# FEU31_Part3.net
KiCad netlist of a schematic drawn in Altium Designer
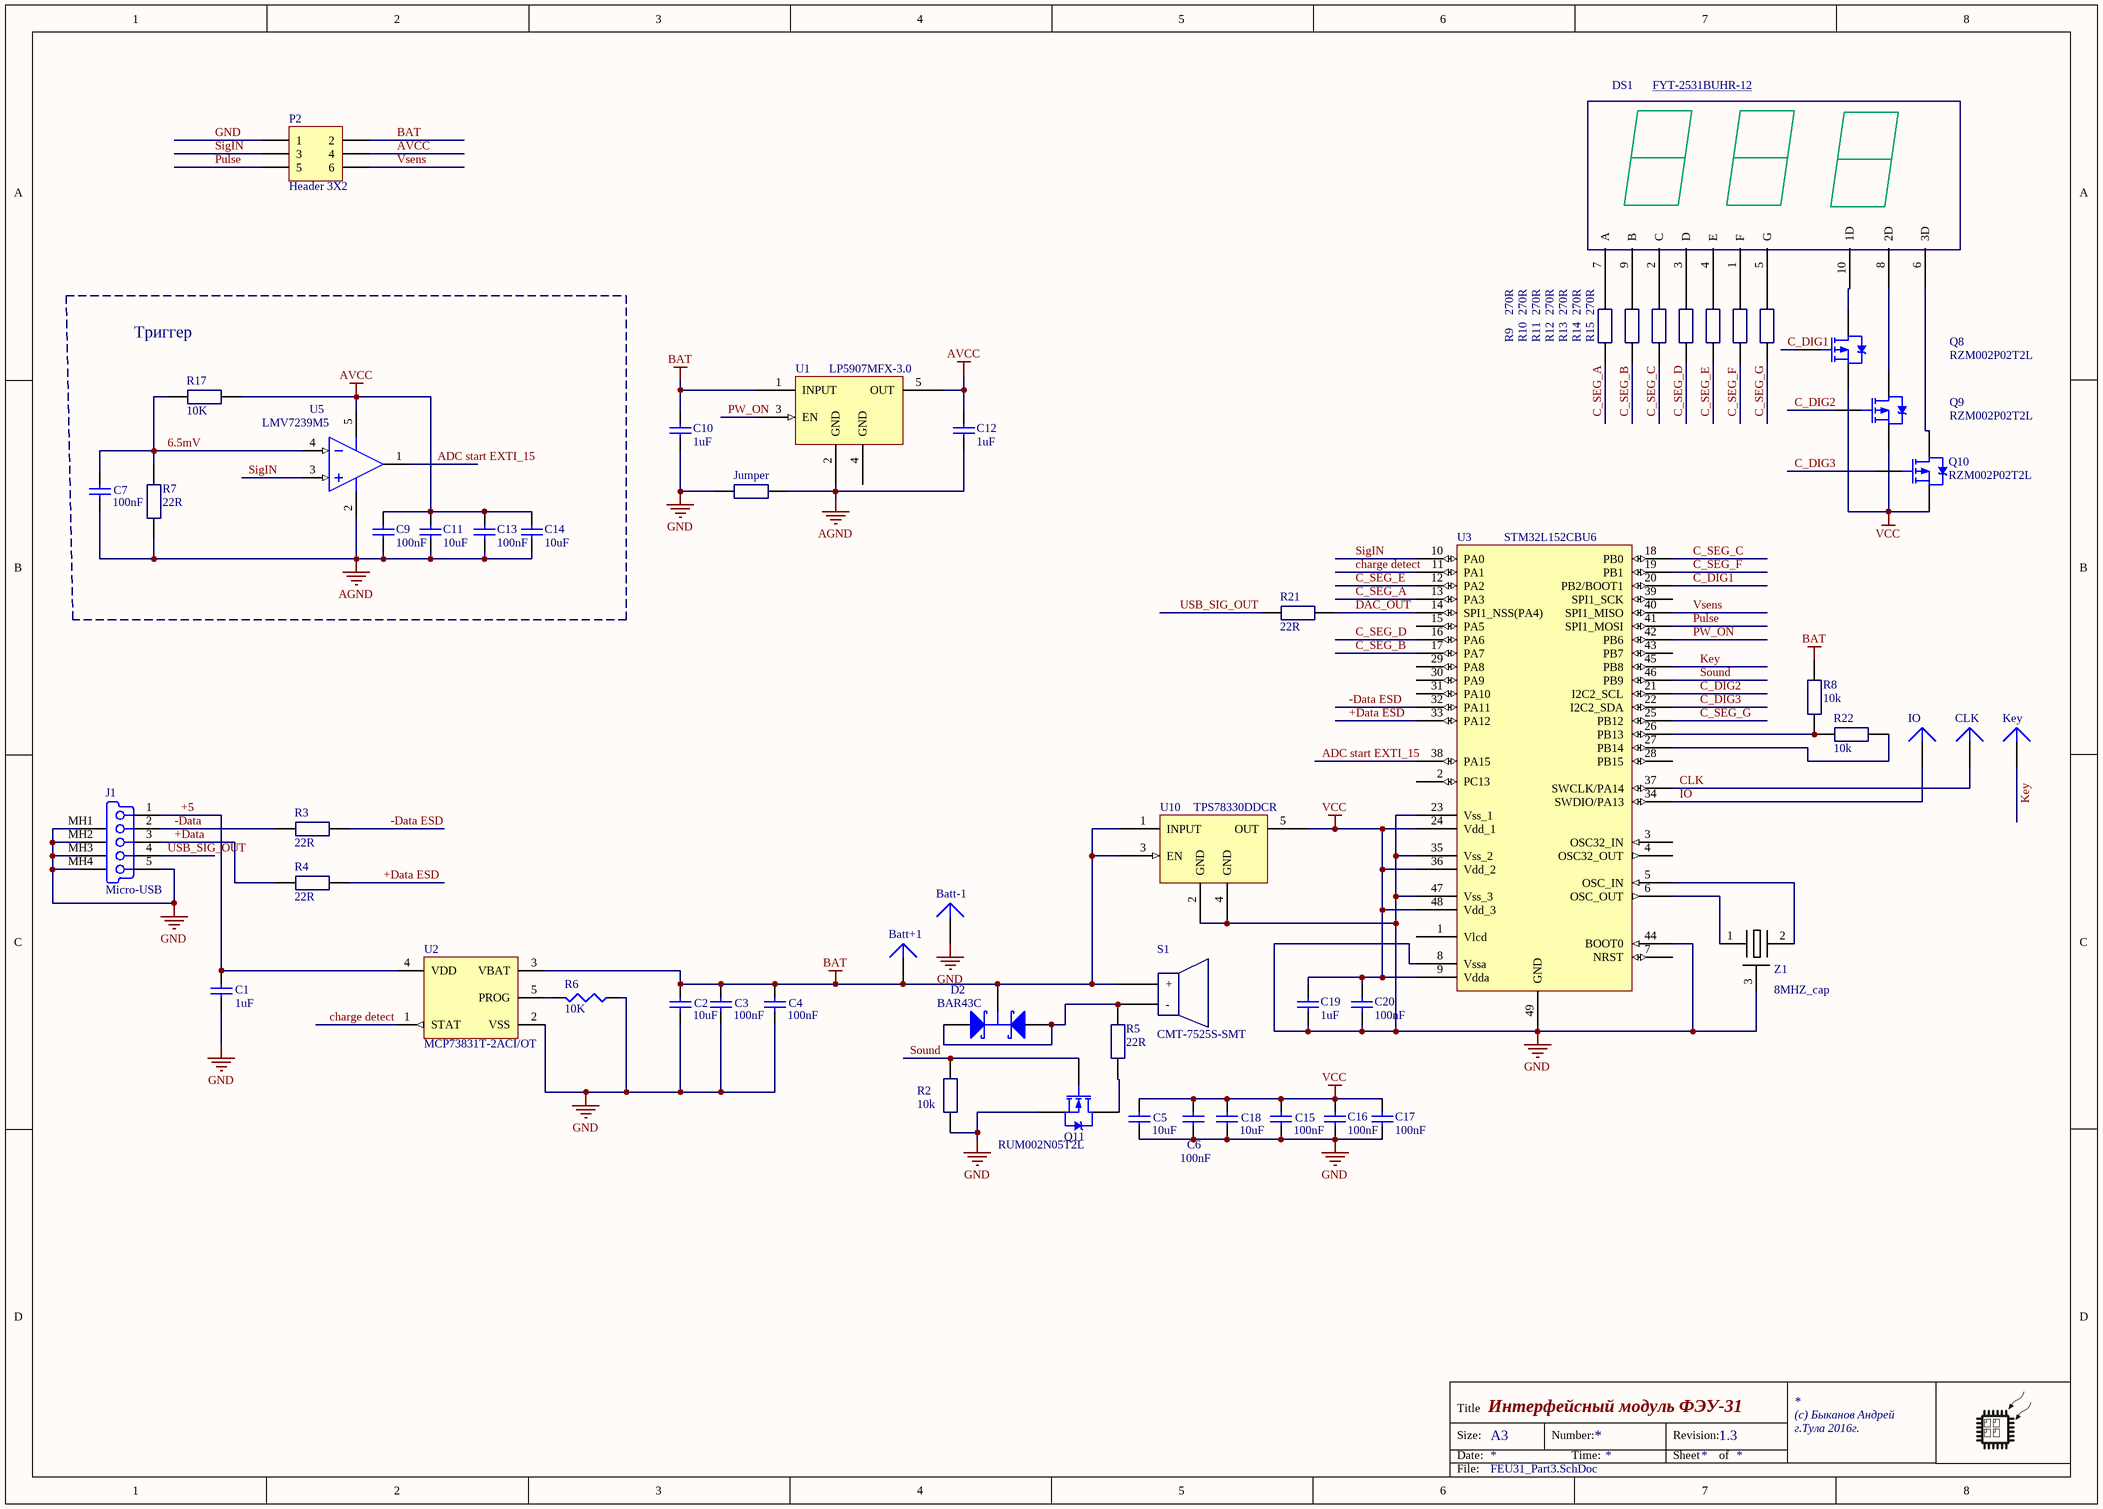
[diagram p0: FEU31_Part3.SchDoc]

(export (version "E")
  (design (tool "Eeschema 10.0.6"))
  (components
    (comp (ref "Batt+1")
      (value "~")
      (footprint "Sensor contact")
      (description "Plug")
      (fields (field (name "PUBLISHER") "Altium Limited"))
      (libsource (lib "Miscellaneous Connectors") (part "Plug"))
    )
    (comp (ref "Batt-1")
      (value "~")
      (footprint "Sensor contact")
      (description "Plug")
      (fields (field (name "PUBLISHER") "Altium Limited"))
      (libsource (lib "Miscellaneous Connectors") (part "Plug"))
    )
    (comp (ref "C1")
      (value "1uF")
      (footprint "0402 AVX")
      (description "Capacitor (Semiconductor SIM Model)")
      (fields (field (name "PUBLISHER") "Altium Limited"))
      (libsource (lib "Miscellaneous Devices") (part "Cap Semi"))
    )
    (comp (ref "C2")
      (value "10uF")
      (footprint "1608[0603]")
      (description "Capacitor (Semiconductor SIM Model)")
      (fields (field (name "PUBLISHER") "Altium Limited"))
      (libsource (lib "Miscellaneous Devices") (part "Cap Semi"))
    )
    (comp (ref "C3")
      (value "100nF")
      (footprint "0402 AVX")
      (description "Capacitor (Semiconductor SIM Model)")
      (fields (field (name "PUBLISHER") "Altium Limited"))
      (libsource (lib "Miscellaneous Devices") (part "Cap Semi"))
    )
    (comp (ref "C4")
      (value "100nF")
      (footprint "0402 AVX")
      (description "Capacitor (Semiconductor SIM Model)")
      (fields (field (name "PUBLISHER") "Altium Limited"))
      (libsource (lib "Miscellaneous Devices") (part "Cap Semi"))
    )
    (comp (ref "C5")
      (value "10uF")
      (footprint "1608[0603]")
      (description "Capacitor (Semiconductor SIM Model)")
      (fields (field (name "PUBLISHER") "Altium Limited"))
      (libsource (lib "Miscellaneous Devices") (part "Cap Semi"))
    )
    (comp (ref "C6")
      (value "100nF")
      (footprint "0402 AVX")
      (description "Capacitor (Semiconductor SIM Model)")
      (fields (field (name "PUBLISHER") "Altium Limited"))
      (libsource (lib "Miscellaneous Devices") (part "Cap Semi"))
    )
    (comp (ref "C7")
      (value "100nF")
      (footprint "0402 AVX")
      (description "Capacitor (Semiconductor SIM Model)")
      (fields (field (name "PUBLISHER") "Altium Limited"))
      (libsource (lib "Miscellaneous Devices") (part "Cap Semi"))
    )
    (comp (ref "C9")
      (value "100nF")
      (footprint "0402 AVX")
      (description "Capacitor (Semiconductor SIM Model)")
      (fields (field (name "PUBLISHER") "Altium Limited"))
      (libsource (lib "Miscellaneous Devices") (part "Cap Semi"))
    )
    (comp (ref "C10")
      (value "1uF")
      (footprint "0402 AVX")
      (description "Capacitor (Semiconductor SIM Model)")
      (fields (field (name "PUBLISHER") "Altium Limited"))
      (libsource (lib "Miscellaneous Devices") (part "Cap Semi"))
    )
    (comp (ref "C11")
      (value "10uF")
      (footprint "1608[0603]")
      (description "Capacitor (Semiconductor SIM Model)")
      (fields (field (name "PUBLISHER") "Altium Limited"))
      (libsource (lib "Miscellaneous Devices") (part "Cap Semi"))
    )
    (comp (ref "C12")
      (value "1uF")
      (footprint "0402 AVX")
      (description "Capacitor (Semiconductor SIM Model)")
      (fields (field (name "PUBLISHER") "Altium Limited"))
      (libsource (lib "Miscellaneous Devices") (part "Cap Semi"))
    )
    (comp (ref "C13")
      (value "100nF")
      (footprint "0402 AVX")
      (description "Capacitor (Semiconductor SIM Model)")
      (fields (field (name "PUBLISHER") "Altium Limited"))
      (libsource (lib "Miscellaneous Devices") (part "Cap Semi"))
    )
    (comp (ref "C14")
      (value "10uF")
      (footprint "1608[0603]")
      (description "Capacitor (Semiconductor SIM Model)")
      (fields (field (name "PUBLISHER") "Altium Limited"))
      (libsource (lib "Miscellaneous Devices") (part "Cap Semi"))
    )
    (comp (ref "C15")
      (value "100nF")
      (footprint "0402 AVX")
      (description "Capacitor (Semiconductor SIM Model)")
      (fields (field (name "PUBLISHER") "Altium Limited"))
      (libsource (lib "Miscellaneous Devices") (part "Cap Semi"))
    )
    (comp (ref "C16")
      (value "100nF")
      (footprint "0402 AVX")
      (description "Capacitor (Semiconductor SIM Model)")
      (fields (field (name "PUBLISHER") "Altium Limited"))
      (libsource (lib "Miscellaneous Devices") (part "Cap Semi"))
    )
    (comp (ref "C17")
      (value "100nF")
      (footprint "0402 AVX")
      (description "Capacitor (Semiconductor SIM Model)")
      (fields (field (name "PUBLISHER") "Altium Limited"))
      (libsource (lib "Miscellaneous Devices") (part "Cap Semi"))
    )
    (comp (ref "C18")
      (value "10uF")
      (footprint "1608[0603]")
      (description "Capacitor (Semiconductor SIM Model)")
      (fields (field (name "PUBLISHER") "Altium Limited"))
      (libsource (lib "Miscellaneous Devices") (part "Cap Semi"))
    )
    (comp (ref "C19")
      (value "1uF")
      (footprint "0402 AVX")
      (description "Capacitor (Semiconductor SIM Model)")
      (fields (field (name "PUBLISHER") "Altium Limited"))
      (libsource (lib "Miscellaneous Devices") (part "Cap Semi"))
    )
    (comp (ref "C20")
      (value "100nF")
      (footprint "0402 AVX")
      (description "Capacitor (Semiconductor SIM Model)")
      (fields (field (name "PUBLISHER") "Altium Limited"))
      (libsource (lib "Miscellaneous Devices") (part "Cap Semi"))
    )
    (comp (ref "CLK")
      (value "~")
      (footprint "Sensor contact")
      (description "Plug")
      (fields (field (name "PUBLISHER") "Altium Limited"))
      (libsource (lib "Miscellaneous Connectors") (part "Plug"))
    )
    (comp (ref "D2")
      (value "BAR43C")
      (footprint "SOT23-3")
      (description "Schottky Barrier Double Diode")
      (fields (field (name "PUBLISHER") "Altium Limited"))
      (libsource (lib "Philips Discrete Diode - Schottky") (part "BAT54C"))
    )
    (comp (ref "DS1")
      (value "FYT-2531BUHR-12")
      (footprint "FYT-2531BUHR-12")
      (description "7-segment 3x indicator")
      (libsource (lib "My SCH library") (part "FYT-2531BUHR-12_1"))
    )
    (comp (ref "IO")
      (value "~")
      (footprint "Sensor contact")
      (description "Plug")
      (fields (field (name "PUBLISHER") "Altium Limited"))
      (libsource (lib "Miscellaneous Connectors") (part "Plug"))
    )
    (comp (ref "J1")
      (value "Micro-USB")
      (footprint "47346-0001")
      (libsource (lib "Molex Serial Bus Mini USB") (part "0481900001"))
    )
    (comp (ref "Jumper")
      (value "~")
      (footprint "0402 jumper")
      (libsource (lib "Микрон-3") (part "Resistor 0805"))
    )
    (comp (ref "Key")
      (value "~")
      (footprint "Sensor contact")
      (description "Plug")
      (fields (field (name "PUBLISHER") "Altium Limited"))
      (libsource (lib "Miscellaneous Connectors") (part "Plug"))
    )
    (comp (ref "P2")
      (value "Header 3X2")
      (footprint "PLS_FLAT_CONN_6")
      (description "Header, 3-Pin, Dual row")
      (fields (field (name "PUBLISHER") "Altium Limited"))
      (libsource (lib "Miscellaneous Connectors") (part "Header 3X2"))
    )
    (comp (ref "Q8")
      (value "RZM002P02T2L")
      (footprint "RUM002N05")
      (description "HEXFET Power MOSFET")
      (fields (field (name "PUBLISHER") "Altium Limited"))
      (libsource (lib "IR Discrete MOSFET - Power") (part "IRLML6401"))
    )
    (comp (ref "Q9")
      (value "RZM002P02T2L")
      (footprint "RUM002N05")
      (description "HEXFET Power MOSFET")
      (fields (field (name "PUBLISHER") "Altium Limited"))
      (libsource (lib "IR Discrete MOSFET - Power") (part "IRLML6401"))
    )
    (comp (ref "Q10")
      (value "RZM002P02T2L")
      (footprint "RUM002N05")
      (description "HEXFET Power MOSFET")
      (fields (field (name "PUBLISHER") "Altium Limited"))
      (libsource (lib "IR Discrete MOSFET - Power") (part "IRLML6401"))
    )
    (comp (ref "Q11")
      (value "RUM002N05T2L")
      (footprint "RUM002N05")
      (description "HEXFET Power MOSFET")
      (fields (field (name "PUBLISHER") "Altium Limited"))
      (libsource (lib "IR Discrete MOSFET - Power") (part "IRLML2402"))
    )
    (comp (ref "R2")
      (value "10k")
      (footprint "1608[0603]")
      (libsource (lib "Микрон-3") (part "Resistor 0805"))
    )
    (comp (ref "R3")
      (value "22R")
      (footprint "1608[0603]")
      (libsource (lib "Микрон-3") (part "Resistor 0805"))
    )
    (comp (ref "R4")
      (value "22R")
      (footprint "1608[0603]")
      (libsource (lib "Микрон-3") (part "Resistor 0805"))
    )
    (comp (ref "R5")
      (value "22R")
      (footprint "1608[0603]")
      (libsource (lib "Микрон-3") (part "Resistor 0805"))
    )
    (comp (ref "R6")
      (value "10K")
      (footprint "J1-0603")
      (description "Resistor")
      (fields (field (name "PUBLISHER") "Altium Limited"))
      (libsource (lib "Miscellaneous Devices") (part "Res3"))
    )
    (comp (ref "R7")
      (value "22R")
      (footprint "1608[0603]")
      (libsource (lib "Микрон-3") (part "Resistor 0805"))
    )
    (comp (ref "R8")
      (value "10k")
      (footprint "1608[0603]")
      (libsource (lib "Микрон-3") (part "Resistor 0805"))
    )
    (comp (ref "R9")
      (value "270R")
      (footprint "1608[0603]")
      (libsource (lib "Микрон-3") (part "Resistor 0805"))
    )
    (comp (ref "R10")
      (value "270R")
      (footprint "1608[0603]")
      (libsource (lib "Микрон-3") (part "Resistor 0805"))
    )
    (comp (ref "R11")
      (value "270R")
      (footprint "1608[0603]")
      (libsource (lib "Микрон-3") (part "Resistor 0805"))
    )
    (comp (ref "R12")
      (value "270R")
      (footprint "1608[0603]")
      (libsource (lib "Микрон-3") (part "Resistor 0805"))
    )
    (comp (ref "R13")
      (value "270R")
      (footprint "1608[0603]")
      (libsource (lib "Микрон-3") (part "Resistor 0805"))
    )
    (comp (ref "R14")
      (value "270R")
      (footprint "1608[0603]")
      (libsource (lib "Микрон-3") (part "Resistor 0805"))
    )
    (comp (ref "R15")
      (value "270R")
      (footprint "1608[0603]")
      (libsource (lib "Микрон-3") (part "Resistor 0805"))
    )
    (comp (ref "R17")
      (value "10K")
      (footprint "1608[0603]")
      (libsource (lib "Микрон-3") (part "Resistor 0805"))
    )
    (comp (ref "R21")
      (value "22R")
      (footprint "1608[0603]_RES")
      (libsource (lib "Микрон-3") (part "Resistor 0805"))
    )
    (comp (ref "R22")
      (value "10k")
      (footprint "1608[0603]")
      (libsource (lib "Микрон-3") (part "Resistor 0805"))
    )
    (comp (ref "S1")
      (value "CMT-7525S-SMT")
      (footprint "CMT-7525S-SMT")
      (libsource (lib "My SCH library") (part "CMT-7525S-SMT"))
    )
    (comp (ref "U1")
      (value "LP5907MFX-3.0")
      (footprint "TPS78330DDCR")
      (libsource (lib "My SCH library") (part "TPS78330DDCR"))
    )
    (comp (ref "U2")
      (value "MCP73831T-2ACI/OT")
      (footprint "SOT-23-OT5_N")
      (fields (field (name "PUBLISHER") "Altium Limited"))
      (libsource (lib "Microchip Power Mgt Battery Management") (part "MCP73831T-2ACI/OT"))
    )
    (comp (ref "U3")
      (value "STM32L152CBU6")
      (footprint "UFQFPN48")
      (libsource (lib "Micron-3.2") (part "STM32L152CBU6"))
    )
    (comp (ref "U5")
      (value "LMV7239M5")
      (footprint "MF05A_N")
      (fields
        (field (name "MANUFACTURER") "National Semiconductor")
        (field (name "PUBLISHER") "Altium Limited")
      )
      (libsource (lib "NSC Amplifier") (part "LMV7239M5"))
    )
    (comp (ref "U10")
      (value "TPS78330DDCR")
      (footprint "TPS78330DDCR")
      (libsource (lib "My SCH library") (part "TPS78330DDCR"))
    )
    (comp (ref "Z1")
      (value "8MHZ_cap")
      (footprint "PRQV8.00CR5010Y000")
      (libsource (lib "My SCH library") (part "8MHZ_cap"))
    )
  )
  (nets
    (net (code "1") (name "/+5") (class "Default")
      (node (ref "C1") (pin "2") (pinfunction "2_2") (pintype "passive"))
      (node (ref "J1") (pin "1") (pinfunction "V_BUS_(5V)_1") (pintype "passive"))
      (node (ref "U2") (pin "4") (pinfunction "VDD_4") (pintype "power_in"))
    )
    (net (code "2") (name "/+Data") (class "Default")
      (node (ref "J1") (pin "3") (pinfunction "D+_3") (pintype "passive"))
      (node (ref "R4") (pin "2") (pinfunction "2_2") (pintype "passive"))
    )
    (net (code "3") (name "/+Data ESD") (class "Default")
      (node (ref "R4") (pin "1") (pinfunction "A_1") (pintype "passive"))
      (node (ref "U3") (pin "33") (pinfunction "PA12_33") (pintype "bidirectional"))
    )
    (net (code "4") (name "/-Data") (class "Default")
      (node (ref "J1") (pin "2") (pinfunction "D-_2") (pintype "passive"))
      (node (ref "R3") (pin "2") (pinfunction "2_2") (pintype "passive"))
    )
    (net (code "5") (name "/-Data ESD") (class "Default")
      (node (ref "R3") (pin "1") (pinfunction "A_1") (pintype "passive"))
      (node (ref "U3") (pin "32") (pinfunction "PA11_32") (pintype "bidirectional"))
    )
    (net (code "6") (name "/6.5mV") (class "Default")
      (node (ref "C7") (pin "1") (pinfunction "1_1") (pintype "passive"))
      (node (ref "R17") (pin "1") (pinfunction "A_1") (pintype "passive"))
      (node (ref "R7") (pin "2") (pinfunction "2_2") (pintype "passive"))
      (node (ref "U5") (pin "4") (pinfunction "IN-_4") (pintype "input"))
    )
    (net (code "7") (name "/ADC start EXTI_15") (class "Default")
      (node (ref "U3") (pin "38") (pinfunction "PA15_38") (pintype "bidirectional"))
      (node (ref "U5") (pin "1") (pinfunction "VOUT_1") (pintype "open_collector"))
    )
    (net (code "8") (name "/CLK") (class "Default")
      (node (ref "CLK") (pin "1") (pinfunction "1_1") (pintype "passive"))
      (node (ref "U3") (pin "37") (pinfunction "SWCLK/PA14_37") (pintype "bidirectional"))
    )
    (net (code "9") (name "/C_DIG1") (class "Default")
      (node (ref "Q8") (pin "1") (pinfunction "G_1") (pintype "passive"))
      (node (ref "U3") (pin "20") (pinfunction "PB2/BOOT1_20") (pintype "bidirectional"))
    )
    (net (code "10") (name "/C_DIG2") (class "Default")
      (node (ref "Q9") (pin "1") (pinfunction "G_1") (pintype "passive"))
      (node (ref "U3") (pin "21") (pinfunction "I2C2_SCL_21") (pintype "bidirectional"))
    )
    (net (code "11") (name "/C_DIG3") (class "Default")
      (node (ref "Q10") (pin "1") (pinfunction "G_1") (pintype "passive"))
      (node (ref "U3") (pin "22") (pinfunction "I2C2_SDA_22") (pintype "bidirectional"))
    )
    (net (code "12") (name "/C_SEG_A") (class "Default")
      (node (ref "R12") (pin "2") (pinfunction "2_2") (pintype "passive"))
      (node (ref "U3") (pin "13") (pinfunction "PA3_13") (pintype "bidirectional"))
    )
    (net (code "13") (name "/C_SEG_B") (class "Default")
      (node (ref "R13") (pin "2") (pinfunction "2_2") (pintype "passive"))
      (node (ref "U3") (pin "17") (pinfunction "PA7_17") (pintype "bidirectional"))
    )
    (net (code "14") (name "/C_SEG_C") (class "Default")
      (node (ref "R11") (pin "2") (pinfunction "2_2") (pintype "passive"))
      (node (ref "U3") (pin "18") (pinfunction "PB0_18") (pintype "bidirectional"))
    )
    (net (code "15") (name "/C_SEG_D") (class "Default")
      (node (ref "R14") (pin "2") (pinfunction "2_2") (pintype "passive"))
      (node (ref "U3") (pin "16") (pinfunction "PA6_16") (pintype "bidirectional"))
    )
    (net (code "16") (name "/C_SEG_E") (class "Default")
      (node (ref "R10") (pin "2") (pinfunction "2_2") (pintype "passive"))
      (node (ref "U3") (pin "12") (pinfunction "PA2_12") (pintype "bidirectional"))
    )
    (net (code "17") (name "/C_SEG_F") (class "Default")
      (node (ref "R15") (pin "2") (pinfunction "2_2") (pintype "passive"))
      (node (ref "U3") (pin "19") (pinfunction "PB1_19") (pintype "bidirectional"))
    )
    (net (code "18") (name "/C_SEG_G") (class "Default")
      (node (ref "R9") (pin "2") (pinfunction "2_2") (pintype "passive"))
      (node (ref "U3") (pin "25") (pinfunction "PB12_25") (pintype "bidirectional"))
    )
    (net (code "19") (name "/DAC_OUT") (class "Default")
      (node (ref "R21") (pin "1") (pinfunction "A_1") (pintype "passive"))
      (node (ref "U3") (pin "14") (pinfunction "SPI1_NSS(PA4)_14") (pintype "bidirectional"))
    )
    (net (code "20") (name "/IO") (class "Default")
      (node (ref "IO") (pin "1") (pinfunction "1_1") (pintype "passive"))
      (node (ref "U3") (pin "34") (pinfunction "SWDIO/PA13_34") (pintype "bidirectional"))
    )
    (net (code "21") (name "/Key") (class "Default")
      (node (ref "Key") (pin "1") (pinfunction "1_1") (pintype "passive"))
      (node (ref "U3") (pin "45") (pinfunction "PB8_45") (pintype "bidirectional"))
    )
    (net (code "22") (name "/PW_ON") (class "Default")
      (node (ref "U1") (pin "3") (pinfunction "EN_3") (pintype "input"))
      (node (ref "U3") (pin "42") (pinfunction "PB6_42") (pintype "bidirectional"))
    )
    (net (code "23") (name "/Pulse") (class "Default")
      (node (ref "P2") (pin "5") (pinfunction "5_5") (pintype "passive"))
      (node (ref "U3") (pin "41") (pinfunction "SPI1_MOSI_41") (pintype "bidirectional"))
    )
    (net (code "24") (name "/SigIN") (class "Default")
      (node (ref "P2") (pin "3") (pinfunction "3_3") (pintype "passive"))
      (node (ref "U3") (pin "10") (pinfunction "PA0_10") (pintype "bidirectional"))
      (node (ref "U5") (pin "3") (pinfunction "IN+_3") (pintype "input"))
    )
    (net (code "25") (name "/Sound") (class "Default")
      (node (ref "Q11") (pin "1") (pinfunction "G_1") (pintype "passive"))
      (node (ref "R2") (pin "1") (pinfunction "A_1") (pintype "passive"))
      (node (ref "U3") (pin "46") (pinfunction "PB9_46") (pintype "bidirectional"))
    )
    (net (code "26") (name "/USB_SIG_OUT") (class "Default")
      (node (ref "J1") (pin "4") (pinfunction "NC_4") (pintype "passive"))
      (node (ref "R21") (pin "2") (pinfunction "2_2") (pintype "passive"))
    )
    (net (code "27") (name "/Vsens") (class "Default")
      (node (ref "P2") (pin "6") (pinfunction "6_6") (pintype "passive"))
      (node (ref "U3") (pin "40") (pinfunction "SPI1_MISO_40") (pintype "bidirectional"))
    )
    (net (code "28") (name "/charge detect") (class "Default")
      (node (ref "U2") (pin "1") (pinfunction "STAT_1") (pintype "output"))
      (node (ref "U3") (pin "11") (pinfunction "PA1_11") (pintype "bidirectional"))
    )
    (net (code "29") (name "AGND") (class "Default")
      (node (ref "C11") (pin "2") (pinfunction "2_2") (pintype "passive"))
      (node (ref "C12") (pin "2") (pinfunction "2_2") (pintype "passive"))
      (node (ref "C13") (pin "2") (pinfunction "2_2") (pintype "passive"))
      (node (ref "C14") (pin "2") (pinfunction "2_2") (pintype "passive"))
      (node (ref "C7") (pin "2") (pinfunction "2_2") (pintype "passive"))
      (node (ref "C9") (pin "2") (pinfunction "2_2") (pintype "passive"))
      (node (ref "Jumper") (pin "1") (pinfunction "A_1") (pintype "passive"))
      (node (ref "R7") (pin "1") (pinfunction "A_1") (pintype "passive"))
      (node (ref "U1") (pin "2") (pinfunction "GND_2") (pintype "power_in"))
      (node (ref "U5") (pin "2") (pinfunction "V-_2") (pintype "power_in"))
    )
    (net (code "30") (name "AVCC") (class "Default")
      (node (ref "C11") (pin "1") (pinfunction "1_1") (pintype "passive"))
      (node (ref "C12") (pin "1") (pinfunction "1_1") (pintype "passive"))
      (node (ref "C13") (pin "1") (pinfunction "1_1") (pintype "passive"))
      (node (ref "C14") (pin "1") (pinfunction "1_1") (pintype "passive"))
      (node (ref "C9") (pin "1") (pinfunction "1_1") (pintype "passive"))
      (node (ref "P2") (pin "4") (pinfunction "4_4") (pintype "passive"))
      (node (ref "R17") (pin "2") (pinfunction "2_2") (pintype "passive"))
      (node (ref "U1") (pin "5") (pinfunction "OUT_5") (pintype "power_in"))
      (node (ref "U5") (pin "5") (pinfunction "V+_5") (pintype "power_in"))
    )
    (net (code "31") (name "BAT") (class "Default")
      (node (ref "Batt+1") (pin "1") (pinfunction "1_1") (pintype "passive"))
      (node (ref "C10") (pin "1") (pinfunction "1_1") (pintype "passive"))
      (node (ref "C2") (pin "1") (pinfunction "1_1") (pintype "passive"))
      (node (ref "C3") (pin "1") (pinfunction "1_1") (pintype "passive"))
      (node (ref "C4") (pin "1") (pinfunction "1_1") (pintype "passive"))
      (node (ref "D2") (pin "3") (pinfunction "K_3") (pintype "passive"))
      (node (ref "P2") (pin "2") (pinfunction "2_2") (pintype "passive"))
      (node (ref "R8") (pin "1") (pinfunction "A_1") (pintype "passive"))
      (node (ref "S1") (pin "+") (pinfunction "+_+") (pintype "passive"))
      (node (ref "U1") (pin "1") (pinfunction "INPUT_1") (pintype "power_in"))
      (node (ref "U10") (pin "1") (pinfunction "INPUT_1") (pintype "power_in"))
      (node (ref "U10") (pin "3") (pinfunction "EN_3") (pintype "input"))
      (node (ref "U2") (pin "3") (pinfunction "VBAT_3") (pintype "power_in"))
    )
    (net (code "32") (name "GND") (class "Default")
      (node (ref "Batt-1") (pin "1") (pinfunction "1_1") (pintype "passive"))
      (node (ref "C1") (pin "1") (pinfunction "1_1") (pintype "passive"))
      (node (ref "C10") (pin "2") (pinfunction "2_2") (pintype "passive"))
      (node (ref "C15") (pin "2") (pinfunction "2_2") (pintype "passive"))
      (node (ref "C16") (pin "2") (pinfunction "2_2") (pintype "passive"))
      (node (ref "C17") (pin "2") (pinfunction "2_2") (pintype "passive"))
      (node (ref "C18") (pin "2") (pinfunction "2_2") (pintype "passive"))
      (node (ref "C19") (pin "2") (pinfunction "2_2") (pintype "passive"))
      (node (ref "C2") (pin "2") (pinfunction "2_2") (pintype "passive"))
      (node (ref "C20") (pin "2") (pinfunction "2_2") (pintype "passive"))
      (node (ref "C3") (pin "2") (pinfunction "2_2") (pintype "passive"))
      (node (ref "C4") (pin "2") (pinfunction "2_2") (pintype "passive"))
      (node (ref "C5") (pin "2") (pinfunction "2_2") (pintype "passive"))
      (node (ref "C6") (pin "2") (pinfunction "2_2") (pintype "passive"))
      (node (ref "J1") (pin "5") (pinfunction "GND_5") (pintype "passive"))
      (node (ref "J1") (pin "MH1") (pinfunction "Tab_MH1") (pintype "passive"))
      (node (ref "J1") (pin "MH2") (pinfunction "Tab_MH2") (pintype "passive"))
      (node (ref "J1") (pin "MH3") (pinfunction "Tab_MH3") (pintype "passive"))
      (node (ref "J1") (pin "MH4") (pinfunction "Tab_MH4") (pintype "passive"))
      (node (ref "Jumper") (pin "2") (pinfunction "2_2") (pintype "passive"))
      (node (ref "P2") (pin "1") (pinfunction "1_1") (pintype "passive"))
      (node (ref "Q11") (pin "2") (pinfunction "S_2") (pintype "passive"))
      (node (ref "R2") (pin "2") (pinfunction "2_2") (pintype "passive"))
      (node (ref "R6") (pin "1") (pinfunction "1_1") (pintype "passive"))
      (node (ref "U10") (pin "2") (pinfunction "GND_2") (pintype "power_in"))
      (node (ref "U10") (pin "4") (pinfunction "GND_4") (pintype "power_in"))
      (node (ref "U2") (pin "2") (pinfunction "VSS_2") (pintype "power_in"))
      (node (ref "U3") (pin "23") (pinfunction "Vss_1_23") (pintype "power_in"))
      (node (ref "U3") (pin "35") (pinfunction "Vss_2_35") (pintype "power_in"))
      (node (ref "U3") (pin "44") (pinfunction "BOOT0_44") (pintype "input"))
      (node (ref "U3") (pin "47") (pinfunction "Vss_3_47") (pintype "power_in"))
      (node (ref "U3") (pin "49") (pinfunction "GND_49") (pintype "power_in"))
      (node (ref "U3") (pin "8") (pinfunction "Vssa_8") (pintype "power_in"))
      (node (ref "Z1") (pin "3") (pinfunction "50_3") (pintype "passive"))
    )
    (net (code "33") (name "Net-(D2-A1)") (class "Default")
      (node (ref "D2") (pin "1") (pinfunction "A1_1") (pintype "passive"))
      (node (ref "D2") (pin "2") (pinfunction "A2_2") (pintype "passive"))
      (node (ref "R5") (pin "1") (pinfunction "A_1") (pintype "passive"))
      (node (ref "S1") (pin "-") (pinfunction "-_-") (pintype "passive"))
    )
    (net (code "34") (name "Net-(DS1-1D)") (class "Default")
      (node (ref "DS1") (pin "10") (pinfunction "1D_10") (pintype "passive"))
      (node (ref "Q8") (pin "3") (pinfunction "D_3") (pintype "passive"))
    )
    (net (code "35") (name "Net-(DS1-2D)") (class "Default")
      (node (ref "DS1") (pin "8") (pinfunction "2D_8") (pintype "passive"))
      (node (ref "Q9") (pin "3") (pinfunction "D_3") (pintype "passive"))
    )
    (net (code "36") (name "Net-(DS1-3D)") (class "Default")
      (node (ref "DS1") (pin "6") (pinfunction "3D_6") (pintype "passive"))
      (node (ref "Q10") (pin "3") (pinfunction "D_3") (pintype "passive"))
    )
    (net (code "37") (name "Net-(DS1-A)") (class "Default")
      (node (ref "DS1") (pin "7") (pinfunction "A_7") (pintype "passive"))
      (node (ref "R12") (pin "1") (pinfunction "A_1") (pintype "passive"))
    )
    (net (code "38") (name "Net-(DS1-B)") (class "Default")
      (node (ref "DS1") (pin "9") (pinfunction "B_9") (pintype "passive"))
      (node (ref "R13") (pin "1") (pinfunction "A_1") (pintype "passive"))
    )
    (net (code "39") (name "Net-(DS1-C)") (class "Default")
      (node (ref "DS1") (pin "2") (pinfunction "C_2") (pintype "passive"))
      (node (ref "R11") (pin "1") (pinfunction "A_1") (pintype "passive"))
    )
    (net (code "40") (name "Net-(DS1-D)") (class "Default")
      (node (ref "DS1") (pin "3") (pinfunction "D_3") (pintype "passive"))
      (node (ref "R14") (pin "1") (pinfunction "A_1") (pintype "passive"))
    )
    (net (code "41") (name "Net-(DS1-E)") (class "Default")
      (node (ref "DS1") (pin "4") (pinfunction "E_4") (pintype "passive"))
      (node (ref "R10") (pin "1") (pinfunction "A_1") (pintype "passive"))
    )
    (net (code "42") (name "Net-(DS1-F)") (class "Default")
      (node (ref "DS1") (pin "1") (pinfunction "F_1") (pintype "passive"))
      (node (ref "R15") (pin "1") (pinfunction "A_1") (pintype "passive"))
    )
    (net (code "43") (name "Net-(DS1-G)") (class "Default")
      (node (ref "DS1") (pin "5") (pinfunction "G_5") (pintype "passive"))
      (node (ref "R9") (pin "1") (pinfunction "A_1") (pintype "passive"))
    )
    (net (code "44") (name "Net-(Q11-D)") (class "Default")
      (node (ref "Q11") (pin "3") (pinfunction "D_3") (pintype "passive"))
      (node (ref "R5") (pin "2") (pinfunction "2_2") (pintype "passive"))
    )
    (net (code "45") (name "Net-(R22-A)") (class "Default")
      (node (ref "R22") (pin "1") (pinfunction "A_1") (pintype "passive"))
      (node (ref "U3") (pin "27") (pinfunction "PB14_27") (pintype "bidirectional"))
    )
    (net (code "46") (name "Net-(U2-PROG)") (class "Default")
      (node (ref "R6") (pin "2") (pinfunction "2_2") (pintype "passive"))
      (node (ref "U2") (pin "5") (pinfunction "PROG_5") (pintype "passive"))
    )
    (net (code "47") (name "Net-(U3-OSC_IN)") (class "Default")
      (node (ref "U3") (pin "5") (pinfunction "OSC_IN_5") (pintype "input"))
      (node (ref "Z1") (pin "2") (pinfunction "2_2") (pintype "passive"))
    )
    (net (code "48") (name "Net-(U3-OSC_OUT)") (class "Default")
      (node (ref "U3") (pin "6") (pinfunction "OSC_OUT_6") (pintype "output"))
      (node (ref "Z1") (pin "1") (pinfunction "50_1") (pintype "passive"))
    )
    (net (code "49") (name "Net-(U3-PB13)") (class "Default")
      (node (ref "R22") (pin "2") (pinfunction "2_2") (pintype "passive"))
      (node (ref "R8") (pin "2") (pinfunction "2_2") (pintype "passive"))
      (node (ref "U3") (pin "26") (pinfunction "PB13_26") (pintype "bidirectional"))
    )
    (net (code "50") (name "VCC") (class "Default")
      (node (ref "C15") (pin "1") (pinfunction "1_1") (pintype "passive"))
      (node (ref "C16") (pin "1") (pinfunction "1_1") (pintype "passive"))
      (node (ref "C17") (pin "1") (pinfunction "1_1") (pintype "passive"))
      (node (ref "C18") (pin "1") (pinfunction "1_1") (pintype "passive"))
      (node (ref "C19") (pin "1") (pinfunction "1_1") (pintype "passive"))
      (node (ref "C20") (pin "1") (pinfunction "1_1") (pintype "passive"))
      (node (ref "C5") (pin "1") (pinfunction "1_1") (pintype "passive"))
      (node (ref "C6") (pin "1") (pinfunction "1_1") (pintype "passive"))
      (node (ref "Q10") (pin "2") (pinfunction "S_2") (pintype "passive"))
      (node (ref "Q8") (pin "2") (pinfunction "S_2") (pintype "passive"))
      (node (ref "Q9") (pin "2") (pinfunction "S_2") (pintype "passive"))
      (node (ref "U10") (pin "5") (pinfunction "OUT_5") (pintype "power_in"))
      (node (ref "U3") (pin "24") (pinfunction "Vdd_1_24") (pintype "power_in"))
      (node (ref "U3") (pin "36") (pinfunction "Vdd_2_36") (pintype "power_in"))
      (node (ref "U3") (pin "48") (pinfunction "Vdd_3_48") (pintype "power_in"))
      (node (ref "U3") (pin "9") (pinfunction "Vdda_9") (pintype "power_in"))
    )
    (net (code "51") (name "unconnected-(U1-GND-Pad4)") (class "Default")
      (node (ref "U1") (pin "4") (pinfunction "GND_4") (pintype "power_in"))
    )
    (net (code "52") (name "unconnected-(U3-NRST-Pad7)") (class "Default")
      (node (ref "U3") (pin "7") (pinfunction "NRST_7") (pintype "bidirectional"))
    )
    (net (code "53") (name "unconnected-(U3-OSC32_IN-Pad3)") (class "Default")
      (node (ref "U3") (pin "3") (pinfunction "OSC32_IN_3") (pintype "input"))
    )
    (net (code "54") (name "unconnected-(U3-OSC32_OUT-Pad4)") (class "Default")
      (node (ref "U3") (pin "4") (pinfunction "OSC32_OUT_4") (pintype "output"))
    )
    (net (code "55") (name "unconnected-(U3-PA5-Pad15)") (class "Default")
      (node (ref "U3") (pin "15") (pinfunction "PA5_15") (pintype "bidirectional"))
    )
    (net (code "56") (name "unconnected-(U3-PA8-Pad29)") (class "Default")
      (node (ref "U3") (pin "29") (pinfunction "PA8_29") (pintype "bidirectional"))
    )
    (net (code "57") (name "unconnected-(U3-PA9-Pad30)") (class "Default")
      (node (ref "U3") (pin "30") (pinfunction "PA9_30") (pintype "bidirectional"))
    )
    (net (code "58") (name "unconnected-(U3-PA10-Pad31)") (class "Default")
      (node (ref "U3") (pin "31") (pinfunction "PA10_31") (pintype "bidirectional"))
    )
    (net (code "59") (name "unconnected-(U3-PB7-Pad43)") (class "Default")
      (node (ref "U3") (pin "43") (pinfunction "PB7_43") (pintype "bidirectional"))
    )
    (net (code "60") (name "unconnected-(U3-PB15-Pad28)") (class "Default")
      (node (ref "U3") (pin "28") (pinfunction "PB15_28") (pintype "bidirectional"))
    )
    (net (code "61") (name "unconnected-(U3-PC13-Pad2)") (class "Default")
      (node (ref "U3") (pin "2") (pinfunction "PC13_2") (pintype "bidirectional"))
    )
    (net (code "62") (name "unconnected-(U3-SPI1_SCK-Pad39)") (class "Default")
      (node (ref "U3") (pin "39") (pinfunction "SPI1_SCK_39") (pintype "bidirectional"))
    )
    (net (code "63") (name "unconnected-(U3-Vlcd-Pad1)") (class "Default")
      (node (ref "U3") (pin "1") (pinfunction "Vlcd_1") (pintype "power_in"))
    )
  )
)
